# x_mas_esquem_tico.net
KiCad netlist of a schematic drawn in Altium Designer
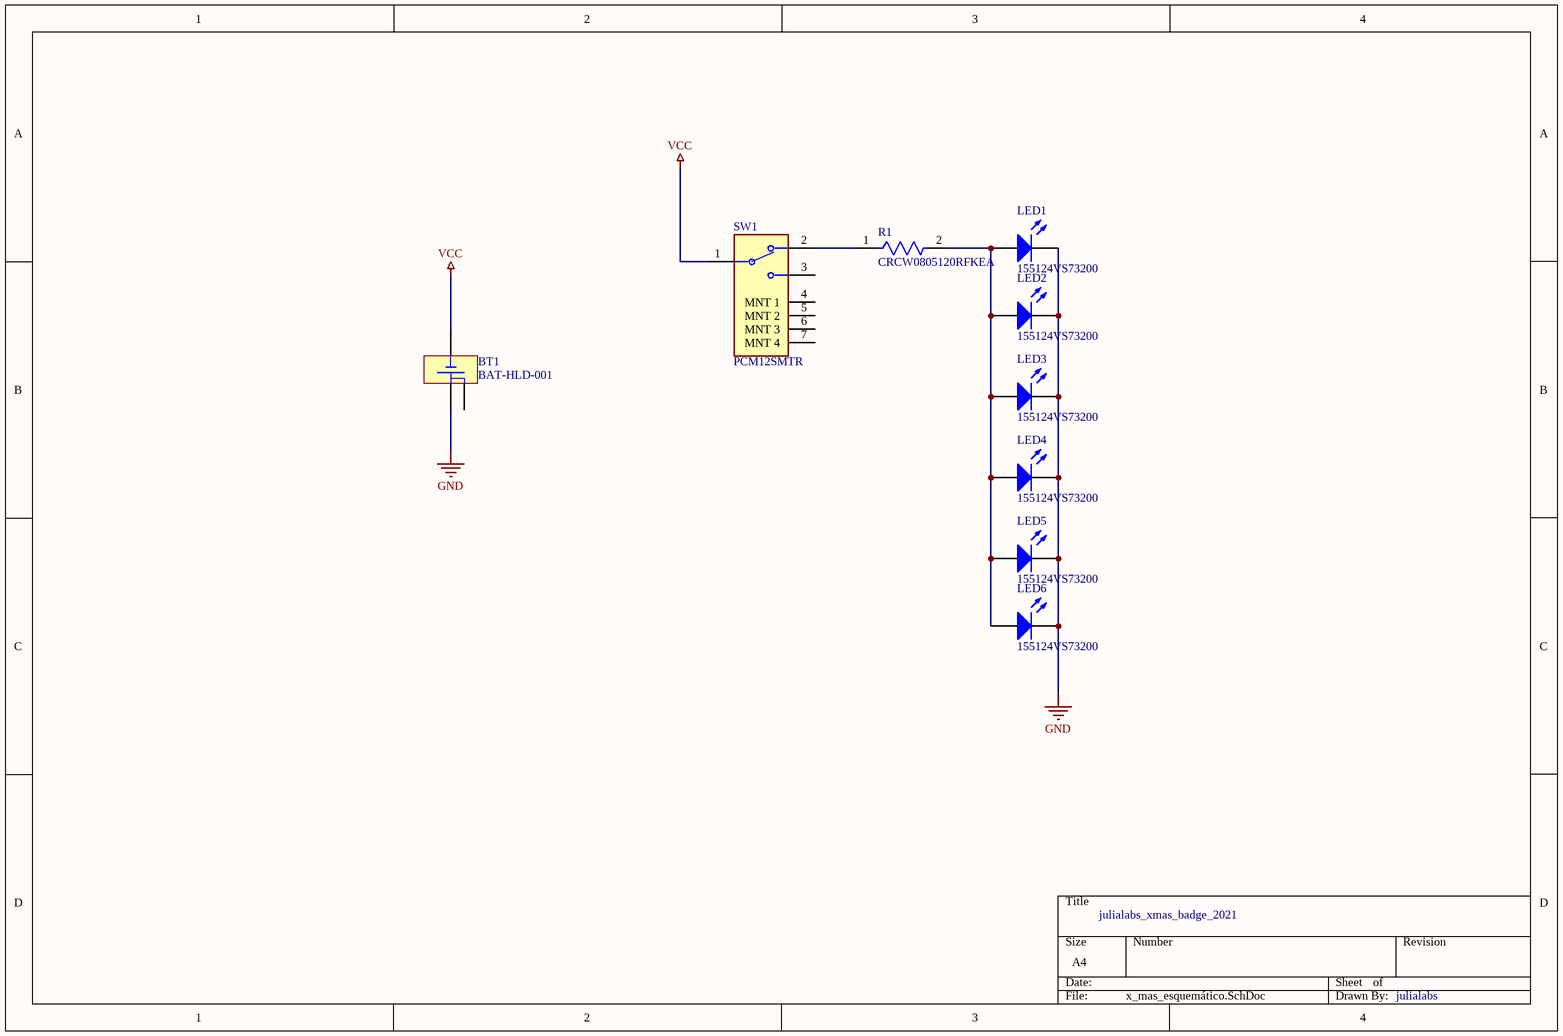
[diagram p0: x_mas_esquemático.SchDoc]

(export (version "E")
  (design (tool "Eeschema 10.0.6"))
  (components
    (comp (ref "BT1")
      (value "BAT-HLD-001")
      (footprint "BATHLD-001")
      (description "20mm Coin Cell Battery Holder")
      (libsource (lib "Altium Content Vault") (part "BATHLD-001"))
    )
    (comp (ref "LED1")
      (value "155124VS73200")
      (footprint "1204")
      (description "SMD Side view mono-color Chip LED-Round , WL-SMSW, Bright Green")
      (fields (field (name "MANUFACTURER") "Wuerth Elektronik"))
      (libsource (lib "Altium Content Vault") (part "WE-LED_K1A2-2"))
    )
    (comp (ref "LED2")
      (value "155124VS73200")
      (footprint "1204")
      (description "SMD Side view mono-color Chip LED-Round , WL-SMSW, Bright Green")
      (fields (field (name "MANUFACTURER") "Wuerth Elektronik"))
      (libsource (lib "Altium Content Vault") (part "WE-LED_K1A2-2"))
    )
    (comp (ref "LED3")
      (value "155124VS73200")
      (footprint "1204")
      (description "SMD Side view mono-color Chip LED-Round , WL-SMSW, Bright Green")
      (fields (field (name "MANUFACTURER") "Wuerth Elektronik"))
      (libsource (lib "Altium Content Vault") (part "WE-LED_K1A2-2"))
    )
    (comp (ref "LED4")
      (value "155124VS73200")
      (footprint "1204")
      (description "SMD Side view mono-color Chip LED-Round , WL-SMSW, Bright Green")
      (fields (field (name "MANUFACTURER") "Wuerth Elektronik"))
      (libsource (lib "Altium Content Vault") (part "WE-LED_K1A2-2"))
    )
    (comp (ref "LED5")
      (value "155124VS73200")
      (footprint "1204")
      (description "SMD Side view mono-color Chip LED-Round , WL-SMSW, Bright Green")
      (fields (field (name "MANUFACTURER") "Wuerth Elektronik"))
      (libsource (lib "Altium Content Vault") (part "WE-LED_K1A2-2"))
    )
    (comp (ref "LED6")
      (value "155124VS73200")
      (footprint "1204")
      (description "SMD Side view mono-color Chip LED-Round , WL-SMSW, Bright Green")
      (fields (field (name "MANUFACTURER") "Wuerth Elektronik"))
      (libsource (lib "Altium Content Vault") (part "WE-LED_K1A2-2"))
    )
    (comp (ref "R1")
      (value "CRCW0805120RFKEA")
      (footprint "FP-CRCW0805-e3-IPC_C")
      (description "RES Thick Film, 120Ω, 1%, 0.125W, 100ppm/°C, 0805")
      (fields (field (name "TOLERANCE") "1%"))
      (libsource (lib "Altium Content Vault") (part "1029c3af85768c4190bb7ad29bc67b5"))
    )
    (comp (ref "SW1")
      (value "PCM12SMTR")
      (footprint "FP-PCM12SMTR-MFG")
      (description "SWITCH SLIDE SPDT 300MA 6V")
      (libsource (lib "Altium Content Vault") (part "1a3f67d7e2b5469b171eeab59ffb4d2"))
    )
  )
  (nets
    (net (code "1") (name "GND") (class "Default")
      (node (ref "BT1") (pin "2") (pinfunction "+_2") (pintype "passive"))
      (node (ref "LED1") (pin "1") (pinfunction "K_1") (pintype "passive"))
      (node (ref "LED2") (pin "1") (pinfunction "K_1") (pintype "passive"))
      (node (ref "LED3") (pin "1") (pinfunction "K_1") (pintype "passive"))
      (node (ref "LED4") (pin "1") (pinfunction "K_1") (pintype "passive"))
      (node (ref "LED5") (pin "1") (pinfunction "K_1") (pintype "passive"))
      (node (ref "LED6") (pin "1") (pinfunction "K_1") (pintype "passive"))
    )
    (net (code "2") (name "Net-(LED1-A)") (class "Default")
      (node (ref "LED1") (pin "2") (pinfunction "A_2") (pintype "passive"))
      (node (ref "LED2") (pin "2") (pinfunction "A_2") (pintype "passive"))
      (node (ref "LED3") (pin "2") (pinfunction "A_2") (pintype "passive"))
      (node (ref "LED4") (pin "2") (pinfunction "A_2") (pintype "passive"))
      (node (ref "LED5") (pin "2") (pinfunction "A_2") (pintype "passive"))
      (node (ref "LED6") (pin "2") (pinfunction "A_2") (pintype "passive"))
      (node (ref "R1") (pin "2") (pinfunction "2_2") (pintype "passive"))
    )
    (net (code "3") (name "Net-(R1-Pad1)") (class "Default")
      (node (ref "R1") (pin "1") (pinfunction "1_1") (pintype "passive"))
      (node (ref "SW1") (pin "2") (pinfunction "2_2") (pintype "passive"))
    )
    (net (code "4") (name "VCC") (class "Default")
      (node (ref "BT1") (pin "1") (pinfunction "-_1") (pintype "passive"))
      (node (ref "SW1") (pin "1") (pinfunction "1_1") (pintype "passive"))
    )
    (net (code "5") (name "unconnected-(BT1-+-Pad3)") (class "Default")
      (node (ref "BT1") (pin "3") (pinfunction "+_3") (pintype "passive"))
    )
    (net (code "6") (name "unconnected-(SW1-MNT_1-Pad4)") (class "Default")
      (node (ref "SW1") (pin "4") (pinfunction "MNT_1_4") (pintype "passive"))
    )
    (net (code "7") (name "unconnected-(SW1-MNT_2-Pad5)") (class "Default")
      (node (ref "SW1") (pin "5") (pinfunction "MNT_2_5") (pintype "passive"))
    )
    (net (code "8") (name "unconnected-(SW1-MNT_3-Pad6)") (class "Default")
      (node (ref "SW1") (pin "6") (pinfunction "MNT_3_6") (pintype "passive"))
    )
    (net (code "9") (name "unconnected-(SW1-MNT_4-Pad7)") (class "Default")
      (node (ref "SW1") (pin "7") (pinfunction "MNT_4_7") (pintype "passive"))
    )
    (net (code "10") (name "unconnected-(SW1-Pad3)") (class "Default")
      (node (ref "SW1") (pin "3") (pinfunction "3_3") (pintype "passive"))
    )
  )
)
